# ETH_Switch.net
KiCad netlist of a schematic drawn in Altium Designer
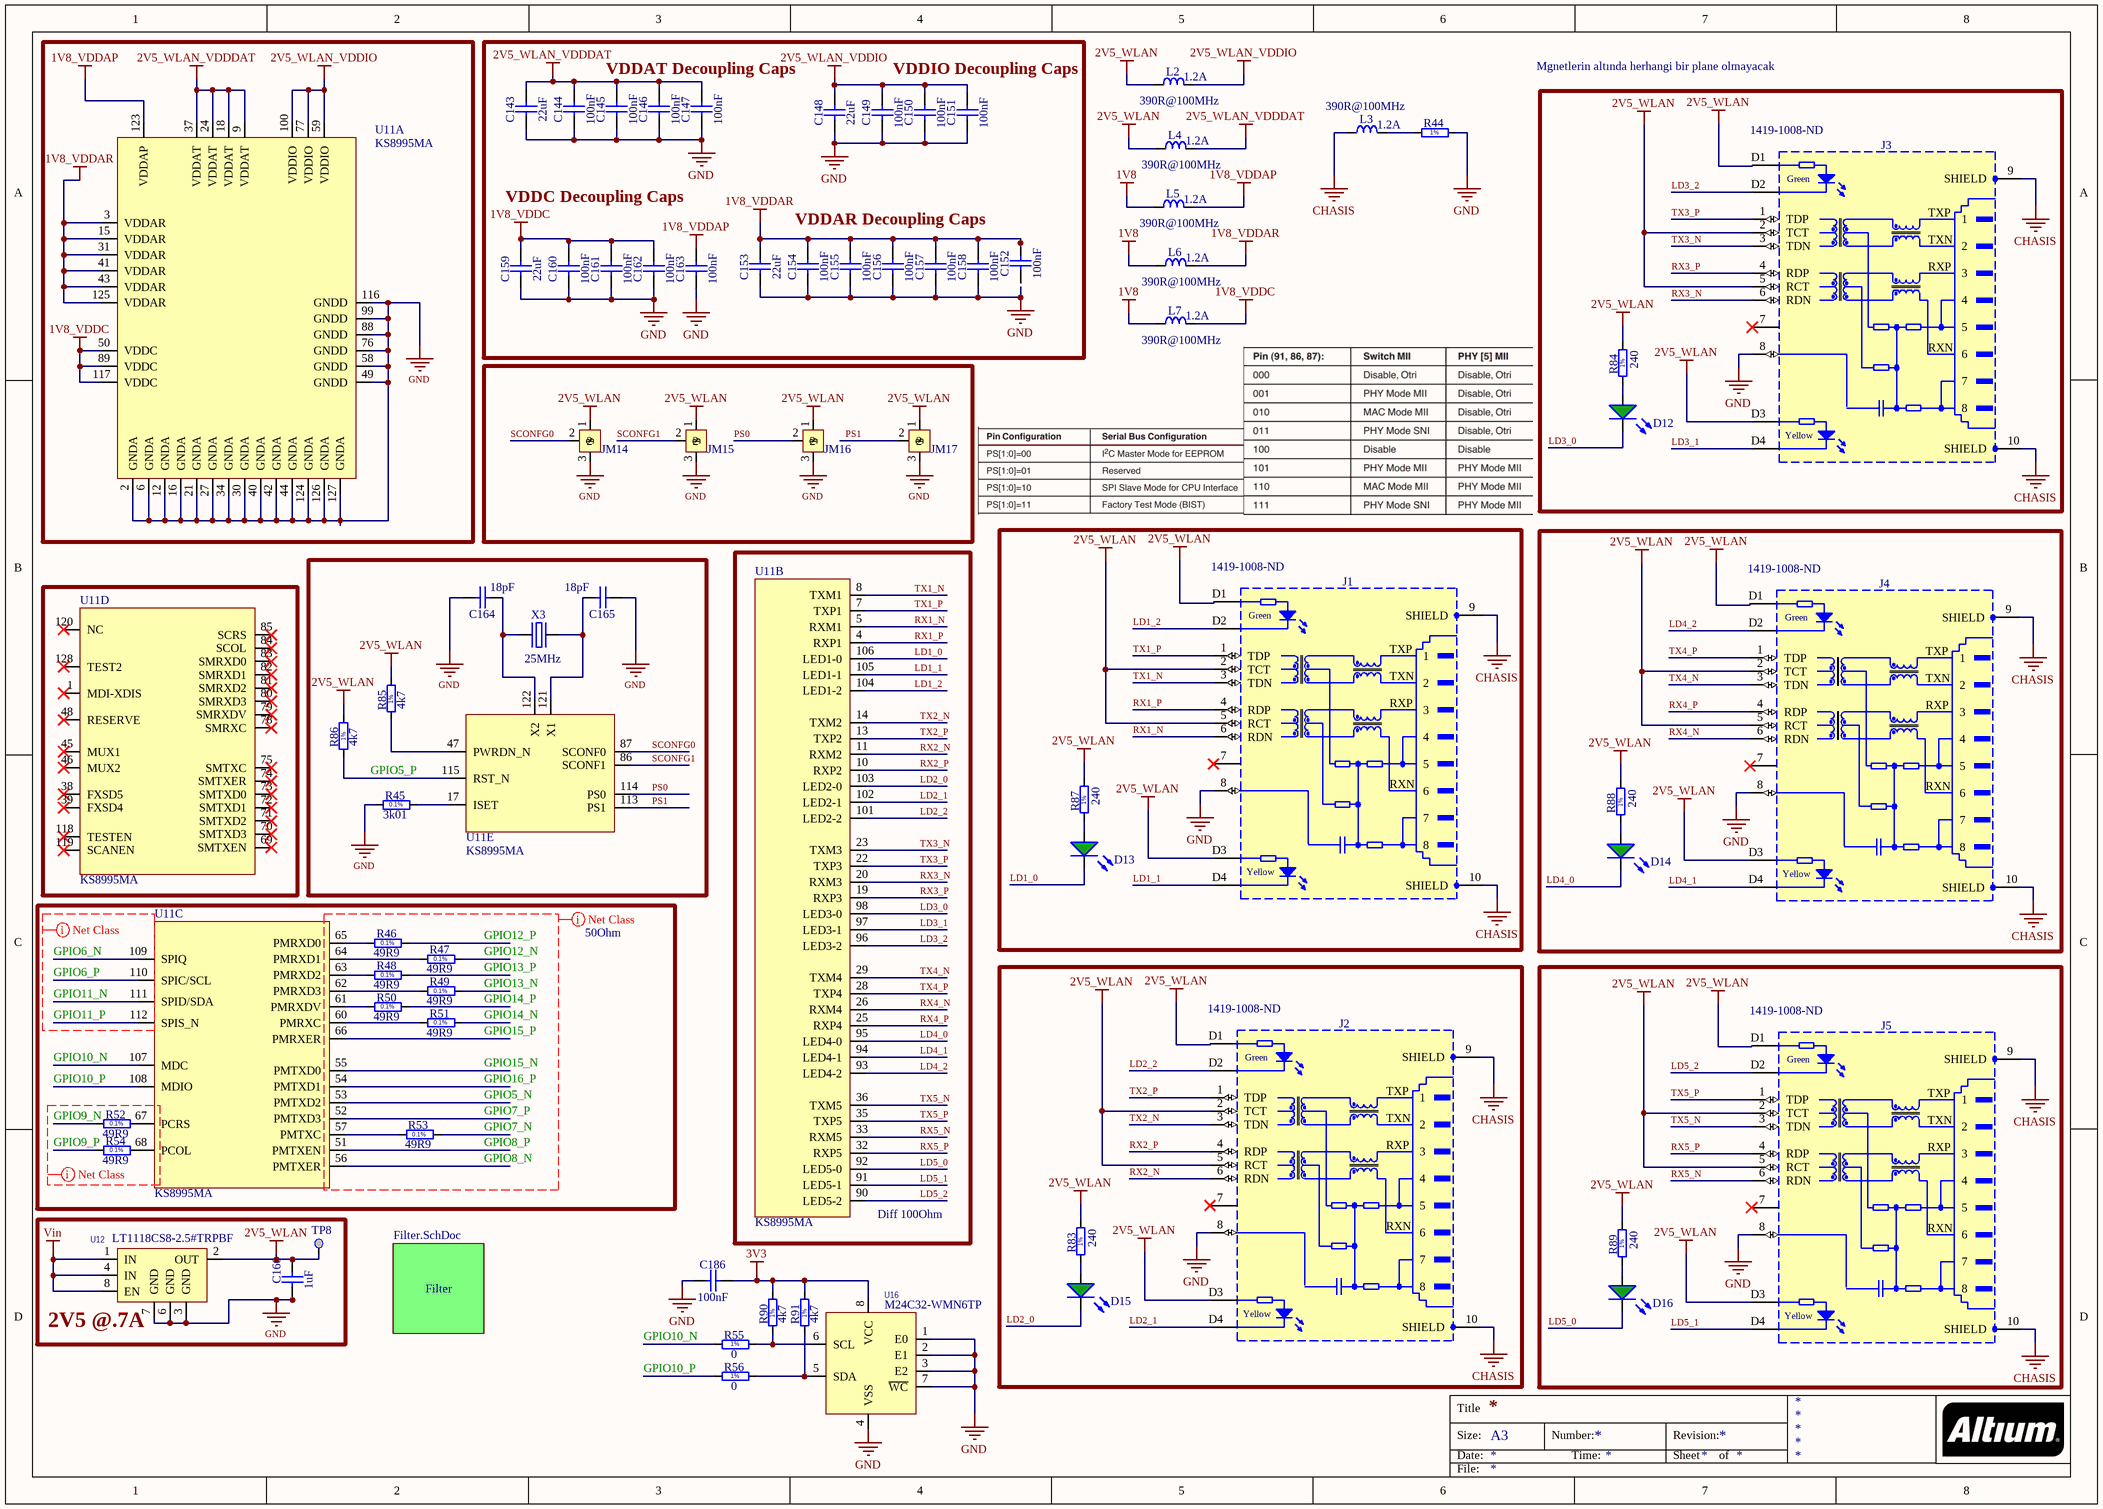
[diagram p0: ETH_Switch.SchDoc]

(export (version "E")
  (design (tool "Eeschema 10.0.6"))
  (components
    (comp (ref "C143")
      (value "22uF")
      (footprint "CAPC2012X135N")
      (description "Non-polarised capacitor")
      (fields (field (name "PART NUMBER") "CC0805_22UF_16V_10%_X5R") (field (name "VOLTAGE") "16V"))
      (libsource (lib "Capacitors") (part "Capacitor - non polarized"))
    )
    (comp (ref "C144")
      (value "100nF")
      (footprint "CAPC1608X87N")
      (description "Non-polarised capacitor")
      (fields (field (name "PART NUMBER") "CC0603_100NF_50V_10%_X7R") (field (name "VOLTAGE") "50V"))
      (libsource (lib "Capacitors") (part "Capacitor - non polarized"))
    )
    (comp (ref "C145")
      (value "100nF")
      (footprint "CAPC1608X87N")
      (description "Non-polarised capacitor")
      (fields (field (name "PART NUMBER") "CC0603_100NF_50V_10%_X7R") (field (name "VOLTAGE") "50V"))
      (libsource (lib "Capacitors") (part "Capacitor - non polarized"))
    )
    (comp (ref "C146")
      (value "100nF")
      (footprint "CAPC1608X87N")
      (description "Non-polarised capacitor")
      (fields (field (name "PART NUMBER") "CC0603_100NF_50V_10%_X7R") (field (name "VOLTAGE") "50V"))
      (libsource (lib "Capacitors") (part "Capacitor - non polarized"))
    )
    (comp (ref "C147")
      (value "100nF")
      (footprint "CAPC1608X87N")
      (description "Non-polarised capacitor")
      (fields (field (name "PART NUMBER") "CC0603_100NF_50V_10%_X7R") (field (name "VOLTAGE") "50V"))
      (libsource (lib "Capacitors") (part "Capacitor - non polarized"))
    )
    (comp (ref "C148")
      (value "22uF")
      (footprint "CAPC2012X135N")
      (description "Non-polarised capacitor")
      (fields (field (name "PART NUMBER") "CC0805_22UF_16V_10%_X5R") (field (name "VOLTAGE") "16V"))
      (libsource (lib "Capacitors") (part "Capacitor - non polarized"))
    )
    (comp (ref "C149")
      (value "100nF")
      (footprint "CAPC1608X87N")
      (description "Non-polarised capacitor")
      (fields (field (name "PART NUMBER") "CC0603_100NF_50V_10%_X7R") (field (name "VOLTAGE") "50V"))
      (libsource (lib "Capacitors") (part "Capacitor - non polarized"))
    )
    (comp (ref "C150")
      (value "100nF")
      (footprint "CAPC1608X87N")
      (description "Non-polarised capacitor")
      (fields (field (name "PART NUMBER") "CC0603_100NF_50V_10%_X7R") (field (name "VOLTAGE") "50V"))
      (libsource (lib "Capacitors") (part "Capacitor - non polarized"))
    )
    (comp (ref "C151")
      (value "100nF")
      (footprint "CAPC1608X87N")
      (description "Non-polarised capacitor")
      (fields (field (name "PART NUMBER") "CC0603_100NF_50V_10%_X7R") (field (name "VOLTAGE") "50V"))
      (libsource (lib "Capacitors") (part "Capacitor - non polarized"))
    )
    (comp (ref "C152")
      (value "100nF")
      (footprint "CAPC1608X87N")
      (description "Non-polarised capacitor")
      (fields (field (name "PART NUMBER") "CC0603_100NF_50V_10%_X7R") (field (name "VOLTAGE") "50V"))
      (libsource (lib "Capacitors") (part "Capacitor - non polarized"))
    )
    (comp (ref "C153")
      (value "22uF")
      (footprint "CAPC2012X135N")
      (description "Non-polarised capacitor")
      (fields (field (name "PART NUMBER") "CC0805_22UF_16V_10%_X5R") (field (name "VOLTAGE") "16V"))
      (libsource (lib "Capacitors") (part "Capacitor - non polarized"))
    )
    (comp (ref "C154")
      (value "100nF")
      (footprint "CAPC1608X87N")
      (description "Non-polarised capacitor")
      (fields (field (name "PART NUMBER") "CC0603_100NF_50V_10%_X7R") (field (name "VOLTAGE") "50V"))
      (libsource (lib "Capacitors") (part "Capacitor - non polarized"))
    )
    (comp (ref "C155")
      (value "100nF")
      (footprint "CAPC1608X87N")
      (description "Non-polarised capacitor")
      (fields (field (name "PART NUMBER") "CC0603_100NF_50V_10%_X7R") (field (name "VOLTAGE") "50V"))
      (libsource (lib "Capacitors") (part "Capacitor - non polarized"))
    )
    (comp (ref "C156")
      (value "100nF")
      (footprint "CAPC1608X87N")
      (description "Non-polarised capacitor")
      (fields (field (name "PART NUMBER") "CC0603_100NF_50V_10%_X7R") (field (name "VOLTAGE") "50V"))
      (libsource (lib "Capacitors") (part "Capacitor - non polarized"))
    )
    (comp (ref "C157")
      (value "100nF")
      (footprint "CAPC1608X87N")
      (description "Non-polarised capacitor")
      (fields (field (name "PART NUMBER") "CC0603_100NF_50V_10%_X7R") (field (name "VOLTAGE") "50V"))
      (libsource (lib "Capacitors") (part "Capacitor - non polarized"))
    )
    (comp (ref "C158")
      (value "100nF")
      (footprint "CAPC1608X87N")
      (description "Non-polarised capacitor")
      (fields (field (name "PART NUMBER") "CC0603_100NF_50V_10%_X7R") (field (name "VOLTAGE") "50V"))
      (libsource (lib "Capacitors") (part "Capacitor - non polarized"))
    )
    (comp (ref "C159")
      (value "22uF")
      (footprint "CAPC2012X135N")
      (description "Non-polarised capacitor")
      (fields (field (name "PART NUMBER") "CC0805_22UF_16V_10%_X5R") (field (name "VOLTAGE") "16V"))
      (libsource (lib "Capacitors") (part "Capacitor - non polarized"))
    )
    (comp (ref "C160")
      (value "100nF")
      (footprint "CAPC1608X87N")
      (description "Non-polarised capacitor")
      (fields (field (name "PART NUMBER") "CC0603_100NF_50V_10%_X7R") (field (name "VOLTAGE") "50V"))
      (libsource (lib "Capacitors") (part "Capacitor - non polarized"))
    )
    (comp (ref "C161")
      (value "100nF")
      (footprint "CAPC1608X87N")
      (description "Non-polarised capacitor")
      (fields (field (name "PART NUMBER") "CC0603_100NF_50V_10%_X7R") (field (name "VOLTAGE") "50V"))
      (libsource (lib "Capacitors") (part "Capacitor - non polarized"))
    )
    (comp (ref "C162")
      (value "100nF")
      (footprint "CAPC1608X87N")
      (description "Non-polarised capacitor")
      (fields (field (name "PART NUMBER") "CC0603_100NF_50V_10%_X7R") (field (name "VOLTAGE") "50V"))
      (libsource (lib "Capacitors") (part "Capacitor - non polarized"))
    )
    (comp (ref "C163")
      (value "100nF")
      (footprint "CAPC1608X87N")
      (description "Non-polarised capacitor")
      (fields (field (name "PART NUMBER") "CC0603_100NF_50V_10%_X7R") (field (name "VOLTAGE") "50V"))
      (libsource (lib "Capacitors") (part "Capacitor - non polarized"))
    )
    (comp (ref "C164")
      (value "18pF")
      (footprint "CAPC1608X87N")
      (description "Non-polarised capacitor")
      (fields (field (name "PART NUMBER") "CC0603_18PF_50V_5%_NP0") (field (name "VOLTAGE") "50V"))
      (libsource (lib "Capacitors") (part "Capacitor - non polarized"))
    )
    (comp (ref "C165")
      (value "18pF")
      (footprint "CAPC1608X87N")
      (description "Non-polarised capacitor")
      (fields (field (name "PART NUMBER") "CC0603_18PF_50V_5%_NP0") (field (name "VOLTAGE") "50V"))
      (libsource (lib "Capacitors") (part "Capacitor - non polarized"))
    )
    (comp (ref "C166")
      (value "1uF")
      (footprint "CAPC1608X87N")
      (description "Non-polarised capacitor")
      (fields (field (name "PART NUMBER") "CC0603_1UF_25V_10%_X7R") (field (name "VOLTAGE") "25V"))
      (libsource (lib "Capacitors") (part "Capacitor - non polarized"))
    )
    (comp (ref "C186")
      (value "100nF")
      (footprint "CAPC1608X87N")
      (description "Non-polarised capacitor")
      (fields (field (name "PART NUMBER") "CC0603_100NF_50V_10%_X7R") (field (name "VOLTAGE") "50V"))
      (libsource (lib "Capacitors") (part "Capacitor - non polarized"))
    )
    (comp (ref "D12")
      (value "LED0603")
      (footprint "LED0603")
      (description "Diode, LED, 0603, Green")
      (fields
        (field (name "MANUFACTURER PART NUMBER") "5988070100F")
        (field (name "MANUFACTURER") "Dialight")
      )
      (libsource (lib "SCHLIB") (part "LED0603"))
    )
    (comp (ref "D13")
      (value "LED0603")
      (footprint "LED0603")
      (description "Diode, LED, 0603, Green")
      (fields
        (field (name "MANUFACTURER PART NUMBER") "5988070100F")
        (field (name "MANUFACTURER") "Dialight")
      )
      (libsource (lib "SCHLIB") (part "LED0603"))
    )
    (comp (ref "D14")
      (value "LED0603")
      (footprint "LED0603")
      (description "Diode, LED, 0603, Green")
      (fields
        (field (name "MANUFACTURER PART NUMBER") "5988070100F")
        (field (name "MANUFACTURER") "Dialight")
      )
      (libsource (lib "SCHLIB") (part "LED0603"))
    )
    (comp (ref "D15")
      (value "LED0603")
      (footprint "LED0603")
      (description "Diode, LED, 0603, Green")
      (fields
        (field (name "MANUFACTURER PART NUMBER") "5988070100F")
        (field (name "MANUFACTURER") "Dialight")
      )
      (libsource (lib "SCHLIB") (part "LED0603"))
    )
    (comp (ref "D16")
      (value "LED0603")
      (footprint "LED0603")
      (description "Diode, LED, 0603, Green")
      (fields
        (field (name "MANUFACTURER PART NUMBER") "5988070100F")
        (field (name "MANUFACTURER") "Dialight")
      )
      (libsource (lib "SCHLIB") (part "LED0603"))
    )
    (comp (ref "J1")
      (value "RJ45")
      (footprint "TYCO_5-6605308-1")
      (fields
        (field (name "PART NUMBER") "TYCO_5-6605308-1")
        (field (name "MANUFACTURER") "TRP Connector B.V.")
        (field (name "MANUFACTURER PART NUMBER") "5-6605308-1")
        (field (name "SUPPLIER PART NUMBER") "1419-1008-ND")
      )
      (libsource (lib "Connectors") (part "TYCO_5-6605308-1"))
    )
    (comp (ref "J2")
      (value "RJ45")
      (footprint "TYCO_5-6605308-1")
      (fields
        (field (name "PART NUMBER") "TYCO_5-6605308-1")
        (field (name "MANUFACTURER") "TRP Connector B.V.")
        (field (name "MANUFACTURER PART NUMBER") "5-6605308-1")
        (field (name "SUPPLIER PART NUMBER") "1419-1008-ND")
      )
      (libsource (lib "Connectors") (part "TYCO_5-6605308-1"))
    )
    (comp (ref "J3")
      (value "RJ45")
      (footprint "TYCO_5-6605308-1")
      (fields
        (field (name "PART NUMBER") "TYCO_5-6605308-1")
        (field (name "MANUFACTURER") "TRP Connector B.V.")
        (field (name "MANUFACTURER PART NUMBER") "5-6605308-1")
        (field (name "SUPPLIER PART NUMBER") "1419-1008-ND")
      )
      (libsource (lib "Connectors") (part "TYCO_5-6605308-1"))
    )
    (comp (ref "J4")
      (value "RJ45")
      (footprint "TYCO_5-6605308-1")
      (fields
        (field (name "PART NUMBER") "TYCO_5-6605308-1")
        (field (name "MANUFACTURER") "TRP Connector B.V.")
        (field (name "MANUFACTURER PART NUMBER") "5-6605308-1")
        (field (name "SUPPLIER PART NUMBER") "1419-1008-ND")
      )
      (libsource (lib "Connectors") (part "TYCO_5-6605308-1"))
    )
    (comp (ref "J5")
      (value "RJ45")
      (footprint "TYCO_5-6605308-1")
      (fields
        (field (name "PART NUMBER") "TYCO_5-6605308-1")
        (field (name "MANUFACTURER") "TRP Connector B.V.")
        (field (name "MANUFACTURER PART NUMBER") "5-6605308-1")
        (field (name "SUPPLIER PART NUMBER") "1419-1008-ND")
      )
      (libsource (lib "Connectors") (part "TYCO_5-6605308-1"))
    )
    (comp (ref "JM14")
      (value "Jumper 0R")
      (footprint "JUMPER_0R")
      (libsource (lib "SCHLIB") (part "Jumper 0R"))
    )
    (comp (ref "JM15")
      (value "Jumper 0R")
      (footprint "JUMPER_0R")
      (libsource (lib "SCHLIB") (part "Jumper 0R"))
    )
    (comp (ref "JM16")
      (value "Jumper 0R")
      (footprint "JUMPER_0R")
      (libsource (lib "SCHLIB") (part "Jumper 0R"))
    )
    (comp (ref "JM17")
      (value "Jumper 0R")
      (footprint "JUMPER_0R")
      (libsource (lib "SCHLIB") (part "Jumper 0R"))
    )
    (comp (ref "L2")
      (value "390R@100MHz")
      (footprint "INDC1608X95N")
      (description "Inductor")
      (fields
        (field (name "PART NUMBER") "IND0603_TDK_MPZ1608R391A")
        (field (name "POWER") "1.2A")
        (field (name "TOLERANCE") "±25%")
      )
      (libsource (lib "Inductors & Transformers") (part "Inductor"))
    )
    (comp (ref "L3")
      (value "390R@100MHz")
      (footprint "INDC1608X95N")
      (description "Inductor")
      (fields
        (field (name "PART NUMBER") "IND0603_TDK_MPZ1608R391A")
        (field (name "POWER") "1.2A")
        (field (name "TOLERANCE") "±25%")
      )
      (libsource (lib "Inductors & Transformers") (part "Inductor"))
    )
    (comp (ref "L4")
      (value "390R@100MHz")
      (footprint "INDC1608X95N")
      (description "Inductor")
      (fields
        (field (name "PART NUMBER") "IND0603_TDK_MPZ1608R391A")
        (field (name "POWER") "1.2A")
        (field (name "TOLERANCE") "±25%")
      )
      (libsource (lib "Inductors & Transformers") (part "Inductor"))
    )
    (comp (ref "L5")
      (value "390R@100MHz")
      (footprint "INDC1608X95N")
      (description "Inductor")
      (fields
        (field (name "PART NUMBER") "IND0603_TDK_MPZ1608R391A")
        (field (name "POWER") "1.2A")
        (field (name "TOLERANCE") "±25%")
      )
      (libsource (lib "Inductors & Transformers") (part "Inductor"))
    )
    (comp (ref "L6")
      (value "390R@100MHz")
      (footprint "INDC1608X95N")
      (description "Inductor")
      (fields
        (field (name "PART NUMBER") "IND0603_TDK_MPZ1608R391A")
        (field (name "POWER") "1.2A")
        (field (name "TOLERANCE") "±25%")
      )
      (libsource (lib "Inductors & Transformers") (part "Inductor"))
    )
    (comp (ref "L7")
      (value "390R@100MHz")
      (footprint "INDC1608X95N")
      (description "Inductor")
      (fields
        (field (name "PART NUMBER") "IND0603_TDK_MPZ1608R391A")
        (field (name "POWER") "1.2A")
        (field (name "TOLERANCE") "±25%")
      )
      (libsource (lib "Inductors & Transformers") (part "Inductor"))
    )
    (comp (ref "R44")
      (value "0")
      (footprint "RESC3216X65N")
      (description "Resistor - 1%")
      (fields
        (field (name "PART NUMBER") "R1206_0R_JUMPER")
        (field (name "MANUFACTURER") "PANASONIC ELECTRONIC COMPONENTS")
      )
      (libsource (lib "Resistors") (part "Resistor - 1%"))
    )
    (comp (ref "R45")
      (value "3k01")
      (footprint "RESC1608X55N")
      (description "Resistor - 0.1%")
      (fields (field (name "PART NUMBER") "R0603_3K01_0.1%_0.063W_10PPM") (field (name "POWER") "0.063W"))
      (libsource (lib "Resistors") (part "Resistor - 0.1%"))
    )
    (comp (ref "R46")
      (value "49R9")
      (footprint "RESC1608X55N")
      (description "Resistor - 0.1%")
      (fields (field (name "PART NUMBER") "R0603_49R9_0.1%_0.063W_10PPM") (field (name "POWER") "0.063W"))
      (libsource (lib "Resistors") (part "Resistor - 0.1%"))
    )
    (comp (ref "R47")
      (value "49R9")
      (footprint "RESC1608X55N")
      (description "Resistor - 0.1%")
      (fields (field (name "PART NUMBER") "R0603_49R9_0.1%_0.063W_10PPM") (field (name "POWER") "0.063W"))
      (libsource (lib "Resistors") (part "Resistor - 0.1%"))
    )
    (comp (ref "R48")
      (value "49R9")
      (footprint "RESC1608X55N")
      (description "Resistor - 0.1%")
      (fields (field (name "PART NUMBER") "R0603_49R9_0.1%_0.063W_10PPM") (field (name "POWER") "0.063W"))
      (libsource (lib "Resistors") (part "Resistor - 0.1%"))
    )
    (comp (ref "R49")
      (value "49R9")
      (footprint "RESC1608X55N")
      (description "Resistor - 0.1%")
      (fields (field (name "PART NUMBER") "R0603_49R9_0.1%_0.063W_10PPM") (field (name "POWER") "0.063W"))
      (libsource (lib "Resistors") (part "Resistor - 0.1%"))
    )
    (comp (ref "R50")
      (value "49R9")
      (footprint "RESC1608X55N")
      (description "Resistor - 0.1%")
      (fields (field (name "PART NUMBER") "R0603_49R9_0.1%_0.063W_10PPM") (field (name "POWER") "0.063W"))
      (libsource (lib "Resistors") (part "Resistor - 0.1%"))
    )
    (comp (ref "R51")
      (value "49R9")
      (footprint "RESC1608X55N")
      (description "Resistor - 0.1%")
      (fields (field (name "PART NUMBER") "R0603_49R9_0.1%_0.063W_10PPM") (field (name "POWER") "0.063W"))
      (libsource (lib "Resistors") (part "Resistor - 0.1%"))
    )
    (comp (ref "R52")
      (value "49R9")
      (footprint "RESC1608X55N")
      (description "Resistor - 0.1%")
      (fields (field (name "PART NUMBER") "R0603_49R9_0.1%_0.063W_10PPM") (field (name "POWER") "0.063W"))
      (libsource (lib "Resistors") (part "Resistor - 0.1%"))
    )
    (comp (ref "R53")
      (value "49R9")
      (footprint "RESC1608X55N")
      (description "Resistor - 0.1%")
      (fields (field (name "PART NUMBER") "R0603_49R9_0.1%_0.063W_10PPM") (field (name "POWER") "0.063W"))
      (libsource (lib "Resistors") (part "Resistor - 0.1%"))
    )
    (comp (ref "R54")
      (value "49R9")
      (footprint "RESC1608X55N")
      (description "Resistor - 0.1%")
      (fields (field (name "PART NUMBER") "R0603_49R9_0.1%_0.063W_10PPM") (field (name "POWER") "0.063W"))
      (libsource (lib "Resistors") (part "Resistor - 0.1%"))
    )
    (comp (ref "R55")
      (value "0")
      (footprint "RESC1608X55N")
      (description "Resistor - 1%")
      (fields (field (name "PART NUMBER") "R0603_0R_JUMPER") (field (name "MANUFACTURER") "MULTICOMP"))
      (libsource (lib "Resistors") (part "Resistor - 1%"))
    )
    (comp (ref "R56")
      (value "0")
      (footprint "RESC1608X55N")
      (description "Resistor - 1%")
      (fields (field (name "PART NUMBER") "R0603_0R_JUMPER") (field (name "MANUFACTURER") "MULTICOMP"))
      (libsource (lib "Resistors") (part "Resistor - 1%"))
    )
    (comp (ref "R83")
      (value "~")
      (footprint "RESC1608X55N")
      (description "RES SMD 240 OHM 5% 1/10W 0603")
      (fields (field (name "MANUFACTURER") "Yageo") (field (name "RESISTANCE (OHMS)") "240"))
      (libsource (lib "Resistors") (part "Resistor - 1%"))
    )
    (comp (ref "R84")
      (value "~")
      (footprint "RESC1608X55N")
      (description "RES SMD 240 OHM 5% 1/10W 0603")
      (fields (field (name "MANUFACTURER") "Yageo") (field (name "RESISTANCE (OHMS)") "240"))
      (libsource (lib "Resistors") (part "Resistor - 1%"))
    )
    (comp (ref "R85")
      (value "4k7")
      (footprint "RESC1608X55N")
      (description "Resistor - 1%")
      (fields (field (name "PART NUMBER") "R0603_4K7_1%_0.1W_100PPM") (field (name "POWER") "0.1W"))
      (libsource (lib "Resistors") (part "Resistor - 1%"))
    )
    (comp (ref "R86")
      (value "4k7")
      (footprint "RESC1608X55N")
      (description "Resistor - 1%")
      (fields (field (name "PART NUMBER") "R0603_4K7_1%_0.1W_100PPM") (field (name "POWER") "0.1W"))
      (libsource (lib "Resistors") (part "Resistor - 1%"))
    )
    (comp (ref "R87")
      (value "~")
      (footprint "RESC1608X55N")
      (description "RES SMD 240 OHM 5% 1/10W 0603")
      (fields (field (name "MANUFACTURER") "Yageo") (field (name "RESISTANCE (OHMS)") "240"))
      (libsource (lib "Resistors") (part "Resistor - 1%"))
    )
    (comp (ref "R88")
      (value "~")
      (footprint "RESC1608X55N")
      (description "RES SMD 240 OHM 5% 1/10W 0603")
      (fields (field (name "MANUFACTURER") "Yageo") (field (name "RESISTANCE (OHMS)") "240"))
      (libsource (lib "Resistors") (part "Resistor - 1%"))
    )
    (comp (ref "R89")
      (value "~")
      (footprint "RESC1608X55N")
      (description "RES SMD 240 OHM 5% 1/10W 0603")
      (fields (field (name "MANUFACTURER") "Yageo") (field (name "RESISTANCE (OHMS)") "240"))
      (libsource (lib "Resistors") (part "Resistor - 1%"))
    )
    (comp (ref "R90")
      (value "4k7")
      (footprint "RESC1608X55N")
      (description "Resistor - 1%")
      (fields (field (name "PART NUMBER") "R0603_4K7_1%_0.1W_100PPM") (field (name "POWER") "0.1W"))
      (libsource (lib "Resistors") (part "Resistor - 1%"))
    )
    (comp (ref "R91")
      (value "4k7")
      (footprint "RESC1608X55N")
      (description "Resistor - 1%")
      (fields (field (name "PART NUMBER") "R0603_4K7_1%_0.1W_100PPM") (field (name "POWER") "0.1W"))
      (libsource (lib "Resistors") (part "Resistor - 1%"))
    )
    (comp (ref "TP8")
      (value "TP")
      (footprint "TP")
      (description "Test Point")
      (libsource (lib "SCHLIB") (part "Test Point"))
    )
    (comp (ref "U11")
      (value "KS8995MA")
      (footprint "KS8995MA")
      (description "IC SWITCH 10/100 5PORT 128PQFP")
      (fields (field (name "MANUFACTURER") "Microchip Technology"))
      (libsource (lib "SCHLIB") (part "KS8995MA"))
    )
    (comp (ref "U12")
      (value "LT1118CS8-2.5")
      (footprint "SO8")
      (description "IC REG LDO 2.5V 0.8A 8SOIC")
      (fields
        (field (name "MANUFACTURER") "Linear Technology")
        (field (name "MANUFACTURER PART NUMBER") "LT1118CS8-2.5#TRPBF")
      )
      (libsource (lib "SCHLIB") (part "LT1118CS8-2.5"))
    )
    (comp (ref "U16")
      (value "M24C32-WMN6TP")
      (footprint "SO8")
      (description "IC EEPROM 32KBIT 400KHZ 8SO")
      (fields
        (field (name "MANUFACTURER") "STMicroelectronics")
        (field (name "MANUFACTURER PART NUMBER") "M24C32-WMN6TP")
      )
      (libsource (lib "SCHLIB") (part "M24C32-WMN6TP"))
    )
    (comp (ref "X3")
      (value "25MHz")
      (footprint "XTAL1140X470X160N")
      (description "Quartz Crystal")
      (fields
        (field (name "PART NUMBER") "XTAL_25MHZ_ABRACON_ABLS-25.000MHZ-B2F-T")
        (field (name "MANUFACTURER") "Abracon LLC")
      )
      (libsource (lib "ICs And Semiconductors") (part "Quartz Crystal"))
    )
  )
  (nets
    (net (code "1") (name "/GPIO5_N") (class "Default")
      (node (ref "U11") (pin "53") (pinfunction "PMTXD2_53") (pintype "passive"))
    )
    (net (code "2") (name "/GPIO5_P") (class "Default")
      (node (ref "R86") (pin "1") (pinfunction "1_1") (pintype "passive"))
      (node (ref "U11") (pin "115") (pinfunction "RST_N_115") (pintype "passive"))
    )
    (net (code "3") (name "/GPIO6_N") (class "Default")
      (node (ref "U11") (pin "109") (pinfunction "SPIQ_109") (pintype "passive"))
    )
    (net (code "4") (name "/GPIO6_P") (class "Default")
      (node (ref "U11") (pin "110") (pinfunction "SPIC/SCL_110") (pintype "passive"))
    )
    (net (code "5") (name "/GPIO7_N") (class "Default")
      (node (ref "R53") (pin "2") (pinfunction "2_2") (pintype "passive"))
    )
    (net (code "6") (name "/GPIO7_P") (class "Default")
      (node (ref "U11") (pin "52") (pinfunction "PMTXD3_52") (pintype "passive"))
    )
    (net (code "7") (name "/GPIO8_N") (class "Default")
      (node (ref "U11") (pin "56") (pinfunction "PMTXER_56") (pintype "passive"))
    )
    (net (code "8") (name "/GPIO8_P") (class "Default")
      (node (ref "U11") (pin "51") (pinfunction "PMTXEN_51") (pintype "passive"))
    )
    (net (code "9") (name "/GPIO9_N") (class "Default")
      (node (ref "R52") (pin "1") (pinfunction "1_1") (pintype "passive"))
    )
    (net (code "10") (name "/GPIO9_P") (class "Default")
      (node (ref "R54") (pin "1") (pinfunction "1_1") (pintype "passive"))
    )
    (net (code "11") (name "/GPIO10_N") (class "Default")
      (node (ref "R55") (pin "1") (pinfunction "1_1") (pintype "passive"))
      (node (ref "U11") (pin "107") (pinfunction "MDC_107") (pintype "passive"))
    )
    (net (code "12") (name "/GPIO10_P") (class "Default")
      (node (ref "R56") (pin "1") (pinfunction "1_1") (pintype "passive"))
      (node (ref "U11") (pin "108") (pinfunction "MDIO_108") (pintype "passive"))
    )
    (net (code "13") (name "/GPIO11_N") (class "Default")
      (node (ref "U11") (pin "111") (pinfunction "SPID/SDA_111") (pintype "passive"))
    )
    (net (code "14") (name "/GPIO11_P") (class "Default")
      (node (ref "U11") (pin "112") (pinfunction "SPIS_N_112") (pintype "passive"))
    )
    (net (code "15") (name "/GPIO12_N") (class "Default")
      (node (ref "R47") (pin "2") (pinfunction "2_2") (pintype "passive"))
    )
    (net (code "16") (name "/GPIO12_P") (class "Default")
      (node (ref "R46") (pin "2") (pinfunction "2_2") (pintype "passive"))
    )
    (net (code "17") (name "/GPIO13_N") (class "Default")
      (node (ref "R49") (pin "2") (pinfunction "2_2") (pintype "passive"))
    )
    (net (code "18") (name "/GPIO13_P") (class "Default")
      (node (ref "R48") (pin "2") (pinfunction "2_2") (pintype "passive"))
    )
    (net (code "19") (name "/GPIO14_N") (class "Default")
      (node (ref "R51") (pin "2") (pinfunction "2_2") (pintype "passive"))
    )
    (net (code "20") (name "/GPIO14_P") (class "Default")
      (node (ref "R50") (pin "2") (pinfunction "2_2") (pintype "passive"))
    )
    (net (code "21") (name "/GPIO15_N") (class "Default")
      (node (ref "U11") (pin "55") (pinfunction "PMTXD0_55") (pintype "passive"))
    )
    (net (code "22") (name "/GPIO15_P") (class "Default")
      (node (ref "U11") (pin "66") (pinfunction "PMRXER_66") (pintype "passive"))
    )
    (net (code "23") (name "/GPIO16_P") (class "Default")
      (node (ref "U11") (pin "54") (pinfunction "PMTXD1_54") (pintype "passive"))
    )
    (net (code "24") (name "/LD1_0") (class "Default")
      (node (ref "D13") (pin "K") (pinfunction "K_K") (pintype "passive"))
      (node (ref "U11") (pin "106") (pinfunction "LED1-0_106") (pintype "passive"))
    )
    (net (code "25") (name "/LD1_1") (class "Default")
      (node (ref "J1") (pin "D4") (pinfunction "D4_D4") (pintype "passive"))
      (node (ref "U11") (pin "105") (pinfunction "LED1-1_105") (pintype "passive"))
    )
    (net (code "26") (name "/LD1_2") (class "Default")
      (node (ref "J1") (pin "D2") (pinfunction "D2_D2") (pintype "passive"))
      (node (ref "U11") (pin "104") (pinfunction "LED1-2_104") (pintype "passive"))
    )
    (net (code "27") (name "/LD2_0") (class "Default")
      (node (ref "D15") (pin "K") (pinfunction "K_K") (pintype "passive"))
      (node (ref "U11") (pin "103") (pinfunction "LED2-0_103") (pintype "passive"))
    )
    (net (code "28") (name "/LD2_1") (class "Default")
      (node (ref "J2") (pin "D4") (pinfunction "D4_D4") (pintype "passive"))
      (node (ref "U11") (pin "102") (pinfunction "LED2-1_102") (pintype "passive"))
    )
    (net (code "29") (name "/LD2_2") (class "Default")
      (node (ref "J2") (pin "D2") (pinfunction "D2_D2") (pintype "passive"))
      (node (ref "U11") (pin "101") (pinfunction "LED2-2_101") (pintype "passive"))
    )
    (net (code "30") (name "/LD3_0") (class "Default")
      (node (ref "D12") (pin "K") (pinfunction "K_K") (pintype "passive"))
      (node (ref "U11") (pin "98") (pinfunction "LED3-0_98") (pintype "passive"))
    )
    (net (code "31") (name "/LD3_1") (class "Default")
      (node (ref "J3") (pin "D4") (pinfunction "D4_D4") (pintype "passive"))
      (node (ref "U11") (pin "97") (pinfunction "LED3-1_97") (pintype "passive"))
    )
    (net (code "32") (name "/LD3_2") (class "Default")
      (node (ref "J3") (pin "D2") (pinfunction "D2_D2") (pintype "passive"))
      (node (ref "U11") (pin "96") (pinfunction "LED3-2_96") (pintype "passive"))
    )
    (net (code "33") (name "/LD4_0") (class "Default")
      (node (ref "D14") (pin "K") (pinfunction "K_K") (pintype "passive"))
      (node (ref "U11") (pin "95") (pinfunction "LED4-0_95") (pintype "passive"))
    )
    (net (code "34") (name "/LD4_1") (class "Default")
      (node (ref "J4") (pin "D4") (pinfunction "D4_D4") (pintype "passive"))
      (node (ref "U11") (pin "94") (pinfunction "LED4-1_94") (pintype "passive"))
    )
    (net (code "35") (name "/LD4_2") (class "Default")
      (node (ref "J4") (pin "D2") (pinfunction "D2_D2") (pintype "passive"))
      (node (ref "U11") (pin "93") (pinfunction "LED4-2_93") (pintype "passive"))
    )
    (net (code "36") (name "/LD5_0") (class "Default")
      (node (ref "D16") (pin "K") (pinfunction "K_K") (pintype "passive"))
      (node (ref "U11") (pin "92") (pinfunction "LED5-0_92") (pintype "passive"))
    )
    (net (code "37") (name "/LD5_1") (class "Default")
      (node (ref "J5") (pin "D4") (pinfunction "D4_D4") (pintype "passive"))
      (node (ref "U11") (pin "91") (pinfunction "LED5-1_91") (pintype "passive"))
    )
    (net (code "38") (name "/LD5_2") (class "Default")
      (node (ref "J5") (pin "D2") (pinfunction "D2_D2") (pintype "passive"))
      (node (ref "U11") (pin "90") (pinfunction "LED5-2_90") (pintype "passive"))
    )
    (net (code "39") (name "/PS0") (class "Default")
      (node (ref "JM16") (pin "2") (pinfunction "2_2") (pintype "passive"))
      (node (ref "U11") (pin "114") (pinfunction "PS0_114") (pintype "passive"))
    )
    (net (code "40") (name "/PS1") (class "Default")
      (node (ref "JM17") (pin "2") (pinfunction "2_2") (pintype "passive"))
      (node (ref "U11") (pin "113") (pinfunction "PS1_113") (pintype "passive"))
    )
    (net (code "41") (name "/RX1_N") (class "Default")
      (node (ref "J1") (pin "6") (pinfunction "RDN_6") (pintype "bidirectional"))
      (node (ref "U11") (pin "5") (pinfunction "RXM1_5") (pintype "passive"))
    )
    (net (code "42") (name "/RX1_P") (class "Default")
      (node (ref "J1") (pin "4") (pinfunction "RDP_4") (pintype "bidirectional"))
      (node (ref "U11") (pin "4") (pinfunction "RXP1_4") (pintype "passive"))
    )
    (net (code "43") (name "/RX2_N") (class "Default")
      (node (ref "J2") (pin "6") (pinfunction "RDN_6") (pintype "bidirectional"))
      (node (ref "U11") (pin "11") (pinfunction "RXM2_11") (pintype "passive"))
    )
    (net (code "44") (name "/RX2_P") (class "Default")
      (node (ref "J2") (pin "4") (pinfunction "RDP_4") (pintype "bidirectional"))
      (node (ref "U11") (pin "10") (pinfunction "RXP2_10") (pintype "passive"))
    )
    (net (code "45") (name "/RX3_N") (class "Default")
      (node (ref "J3") (pin "6") (pinfunction "RDN_6") (pintype "bidirectional"))
      (node (ref "U11") (pin "20") (pinfunction "RXM3_20") (pintype "passive"))
    )
    (net (code "46") (name "/RX3_P") (class "Default")
      (node (ref "J3") (pin "4") (pinfunction "RDP_4") (pintype "bidirectional"))
      (node (ref "U11") (pin "19") (pinfunction "RXP3_19") (pintype "passive"))
    )
    (net (code "47") (name "/RX4_N") (class "Default")
      (node (ref "J4") (pin "6") (pinfunction "RDN_6") (pintype "bidirectional"))
      (node (ref "U11") (pin "26") (pinfunction "RXM4_26") (pintype "passive"))
    )
    (net (code "48") (name "/RX4_P") (class "Default")
      (node (ref "J4") (pin "4") (pinfunction "RDP_4") (pintype "bidirectional"))
      (node (ref "U11") (pin "25") (pinfunction "RXP4_25") (pintype "passive"))
    )
    (net (code "49") (name "/RX5_N") (class "Default")
      (node (ref "J5") (pin "6") (pinfunction "RDN_6") (pintype "bidirectional"))
      (node (ref "U11") (pin "33") (pinfunction "RXM5_33") (pintype "passive"))
    )
    (net (code "50") (name "/RX5_P") (class "Default")
      (node (ref "J5") (pin "4") (pinfunction "RDP_4") (pintype "bidirectional"))
      (node (ref "U11") (pin "32") (pinfunction "RXP5_32") (pintype "passive"))
    )
    (net (code "51") (name "/SCONFG0") (class "Default")
      (node (ref "JM14") (pin "2") (pinfunction "2_2") (pintype "passive"))
      (node (ref "U11") (pin "87") (pinfunction "SCONF0_87") (pintype "passive"))
    )
    (net (code "52") (name "/SCONFG1") (class "Default")
      (node (ref "JM15") (pin "2") (pinfunction "2_2") (pintype "passive"))
      (node (ref "U11") (pin "86") (pinfunction "SCONF1_86") (pintype "passive"))
    )
    (net (code "53") (name "/TX1_N") (class "Default")
      (node (ref "J1") (pin "3") (pinfunction "TDN_3") (pintype "bidirectional"))
      (node (ref "U11") (pin "8") (pinfunction "TXM1_8") (pintype "passive"))
    )
    (net (code "54") (name "/TX1_P") (class "Default")
      (node (ref "J1") (pin "1") (pinfunction "TDP_1") (pintype "bidirectional"))
      (node (ref "U11") (pin "7") (pinfunction "TXP1_7") (pintype "passive"))
    )
    (net (code "55") (name "/TX2_N") (class "Default")
      (node (ref "J2") (pin "3") (pinfunction "TDN_3") (pintype "bidirectional"))
      (node (ref "U11") (pin "14") (pinfunction "TXM2_14") (pintype "passive"))
    )
    (net (code "56") (name "/TX2_P") (class "Default")
      (node (ref "J2") (pin "1") (pinfunction "TDP_1") (pintype "bidirectional"))
      (node (ref "U11") (pin "13") (pinfunction "TXP2_13") (pintype "passive"))
    )
    (net (code "57") (name "/TX3_N") (class "Default")
      (node (ref "J3") (pin "3") (pinfunction "TDN_3") (pintype "bidirectional"))
      (node (ref "U11") (pin "23") (pinfunction "TXM3_23") (pintype "passive"))
    )
    (net (code "58") (name "/TX3_P") (class "Default")
      (node (ref "J3") (pin "1") (pinfunction "TDP_1") (pintype "bidirectional"))
      (node (ref "U11") (pin "22") (pinfunction "TXP3_22") (pintype "passive"))
    )
    (net (code "59") (name "/TX4_N") (class "Default")
      (node (ref "J4") (pin "3") (pinfunction "TDN_3") (pintype "bidirectional"))
      (node (ref "U11") (pin "29") (pinfunction "TXM4_29") (pintype "passive"))
    )
    (net (code "60") (name "/TX4_P") (class "Default")
      (node (ref "J4") (pin "1") (pinfunction "TDP_1") (pintype "bidirectional"))
      (node (ref "U11") (pin "28") (pinfunction "TXP4_28") (pintype "passive"))
    )
    (net (code "61") (name "/TX5_N") (class "Default")
      (node (ref "J5") (pin "3") (pinfunction "TDN_3") (pintype "bidirectional"))
      (node (ref "U11") (pin "36") (pinfunction "TXM5_36") (pintype "passive"))
    )
    (net (code "62") (name "/TX5_P") (class "Default")
      (node (ref "J5") (pin "1") (pinfunction "TDP_1") (pintype "bidirectional"))
      (node (ref "U11") (pin "35") (pinfunction "TXP5_35") (pintype "passive"))
    )
    (net (code "63") (name "1V8") (class "Default")
      (node (ref "L5") (pin "1") (pinfunction "1_1") (pintype "passive"))
      (node (ref "L6") (pin "1") (pinfunction "1_1") (pintype "passive"))
      (node (ref "L7") (pin "1") (pinfunction "1_1") (pintype "passive"))
    )
    (net (code "64") (name "1V8_VDDAP") (class "Default")
      (node (ref "C163") (pin "2") (pinfunction "2_2") (pintype "passive"))
      (node (ref "L5") (pin "2") (pinfunction "2_2") (pintype "passive"))
      (node (ref "U11") (pin "123") (pinfunction "VDDAP_123") (pintype "passive"))
    )
    (net (code "65") (name "1V8_VDDAR") (class "Default")
      (node (ref "C152") (pin "2") (pinfunction "2_2") (pintype "passive"))
      (node (ref "C153") (pin "2") (pinfunction "2_2") (pintype "passive"))
      (node (ref "C154") (pin "2") (pinfunction "2_2") (pintype "passive"))
      (node (ref "C155") (pin "2") (pinfunction "2_2") (pintype "passive"))
      (node (ref "C156") (pin "2") (pinfunction "2_2") (pintype "passive"))
      (node (ref "C157") (pin "2") (pinfunction "2_2") (pintype "passive"))
      (node (ref "C158") (pin "2") (pinfunction "2_2") (pintype "passive"))
      (node (ref "L6") (pin "2") (pinfunction "2_2") (pintype "passive"))
      (node (ref "U11") (pin "125") (pinfunction "VDDAR_125") (pintype "passive"))
      (node (ref "U11") (pin "15") (pinfunction "VDDAR_15") (pintype "passive"))
      (node (ref "U11") (pin "3") (pinfunction "VDDAR_3") (pintype "passive"))
      (node (ref "U11") (pin "31") (pinfunction "VDDAR_31") (pintype "passive"))
      (node (ref "U11") (pin "41") (pinfunction "VDDAR_41") (pintype "passive"))
      (node (ref "U11") (pin "43") (pinfunction "VDDAR_43") (pintype "passive"))
    )
    (net (code "66") (name "1V8_VDDC") (class "Default")
      (node (ref "C159") (pin "2") (pinfunction "2_2") (pintype "passive"))
      (node (ref "C160") (pin "2") (pinfunction "2_2") (pintype "passive"))
      (node (ref "C161") (pin "2") (pinfunction "2_2") (pintype "passive"))
      (node (ref "C162") (pin "2") (pinfunction "2_2") (pintype "passive"))
      (node (ref "L7") (pin "2") (pinfunction "2_2") (pintype "passive"))
      (node (ref "U11") (pin "117") (pinfunction "VDDC_117") (pintype "passive"))
      (node (ref "U11") (pin "50") (pinfunction "VDDC_50") (pintype "passive"))
      (node (ref "U11") (pin "89") (pinfunction "VDDC_89") (pintype "passive"))
    )
    (net (code "67") (name "2V5_WLAN") (class "Default")
      (node (ref "C166") (pin "2") (pinfunction "2_2") (pintype "passive"))
      (node (ref "J1") (pin "2") (pinfunction "TCT_2") (pintype "bidirectional"))
      (node (ref "J1") (pin "5") (pinfunction "RCT_5") (pintype "bidirectional"))
      (node (ref "J1") (pin "D1") (pinfunction "D1_D1") (pintype "passive"))
      (node (ref "J1") (pin "D3") (pinfunction "D3_D3") (pintype "passive"))
      (node (ref "J2") (pin "2") (pinfunction "TCT_2") (pintype "bidirectional"))
      (node (ref "J2") (pin "5") (pinfunction "RCT_5") (pintype "bidirectional"))
      (node (ref "J2") (pin "D1") (pinfunction "D1_D1") (pintype "passive"))
      (node (ref "J2") (pin "D3") (pinfunction "D3_D3") (pintype "passive"))
      (node (ref "J3") (pin "2") (pinfunction "TCT_2") (pintype "bidirectional"))
      (node (ref "J3") (pin "5") (pinfunction "RCT_5") (pintype "bidirectional"))
      (node (ref "J3") (pin "D1") (pinfunction "D1_D1") (pintype "passive"))
      (node (ref "J3") (pin "D3") (pinfunction "D3_D3") (pintype "passive"))
      (node (ref "J4") (pin "2") (pinfunction "TCT_2") (pintype "bidirectional"))
      (node (ref "J4") (pin "5") (pinfunction "RCT_5") (pintype "bidirectional"))
      (node (ref "J4") (pin "D1") (pinfunction "D1_D1") (pintype "passive"))
      (node (ref "J4") (pin "D3") (pinfunction "D3_D3") (pintype "passive"))
      (node (ref "J5") (pin "2") (pinfunction "TCT_2") (pintype "bidirectional"))
      (node (ref "J5") (pin "5") (pinfunction "RCT_5") (pintype "bidirectional"))
      (node (ref "J5") (pin "D1") (pinfunction "D1_D1") (pintype "passive"))
      (node (ref "J5") (pin "D3") (pinfunction "D3_D3") (pintype "passive"))
      (node (ref "JM14") (pin "1") (pinfunction "1_1") (pintype "passive"))
      (node (ref "JM15") (pin "1") (pinfunction "1_1") (pintype "passive"))
      (node (ref "JM16") (pin "1") (pinfunction "1_1") (pintype "passive"))
      (node (ref "JM17") (pin "1") (pinfunction "1_1") (pintype "passive"))
      (node (ref "L2") (pin "1") (pinfunction "1_1") (pintype "passive"))
      (node (ref "L4") (pin "1") (pinfunction "1_1") (pintype "passive"))
      (node (ref "R83") (pin "2") (pinfunction "2_2") (pintype "passive"))
      (node (ref "R84") (pin "2") (pinfunction "2_2") (pintype "passive"))
      (node (ref "R85") (pin "2") (pinfunction "2_2") (pintype "passive"))
      (node (ref "R86") (pin "2") (pinfunction "2_2") (pintype "passive"))
      (node (ref "R87") (pin "2") (pinfunction "2_2") (pintype "passive"))
      (node (ref "R88") (pin "2") (pinfunction "2_2") (pintype "passive"))
      (node (ref "R89") (pin "2") (pinfunction "2_2") (pintype "passive"))
      (node (ref "TP8") (pin "1") (pinfunction "1_1") (pintype "passive"))
      (node (ref "U12") (pin "2") (pinfunction "OUT_2") (pintype "passive"))
    )
    (net (code "68") (name "2V5_WLAN_VDDDAT") (class "Default")
      (node (ref "C143") (pin "2") (pinfunction "2_2") (pintype "passive"))
      (node (ref "C144") (pin "2") (pinfunction "2_2") (pintype "passive"))
      (node (ref "C145") (pin "2") (pinfunction "2_2") (pintype "passive"))
      (node (ref "C146") (pin "2") (pinfunction "2_2") (pintype "passive"))
      (node (ref "C147") (pin "2") (pinfunction "2_2") (pintype "passive"))
      (node (ref "L4") (pin "2") (pinfunction "2_2") (pintype "passive"))
      (node (ref "U11") (pin "18") (pinfunction "VDDAT_18") (pintype "passive"))
      (node (ref "U11") (pin "24") (pinfunction "VDDAT_24") (pintype "passive"))
      (node (ref "U11") (pin "37") (pinfunction "VDDAT_37") (pintype "passive"))
      (node (ref "U11") (pin "9") (pinfunction "VDDAT_9") (pintype "passive"))
    )
    (net (code "69") (name "2V5_WLAN_VDDIO") (class "Default")
      (node (ref "C148") (pin "2") (pinfunction "2_2") (pintype "passive"))
      (node (ref "C149") (pin "2") (pinfunction "2_2") (pintype "passive"))
      (node (ref "C150") (pin "2") (pinfunction "2_2") (pintype "passive"))
      (node (ref "C151") (pin "2") (pinfunction "2_2") (pintype "passive"))
      (node (ref "L2") (pin "2") (pinfunction "2_2") (pintype "passive"))
      (node (ref "U11") (pin "100") (pinfunction "VDDIO_100") (pintype "passive"))
      (node (ref "U11") (pin "59") (pinfunction "VDDIO_59") (pintype "passive"))
      (node (ref "U11") (pin "77") (pinfunction "VDDIO_77") (pintype "passive"))
    )
    (net (code "70") (name "3V3") (class "Default")
      (node (ref "C186") (pin "2") (pinfunction "2_2") (pintype "passive"))
      (node (ref "R90") (pin "2") (pinfunction "2_2") (pintype "passive"))
      (node (ref "R91") (pin "2") (pinfunction "2_2") (pintype "passive"))
      (node (ref "U16") (pin "8") (pinfunction "VCC_8") (pintype "passive"))
    )
    (net (code "71") (name "CHASIS") (class "Default")
      (node (ref "J1") (pin "10") (pinfunction "SHIELD_10") (pintype "power_in"))
      (node (ref "J1") (pin "9") (pinfunction "SHIELD_9") (pintype "power_in"))
      (node (ref "J2") (pin "10") (pinfunction "SHIELD_10") (pintype "power_in"))
      (node (ref "J2") (pin "9") (pinfunction "SHIELD_9") (pintype "power_in"))
      (node (ref "J3") (pin "10") (pinfunction "SHIELD_10") (pintype "power_in"))
      (node (ref "J3") (pin "9") (pinfunction "SHIELD_9") (pintype "power_in"))
      (node (ref "J4") (pin "10") (pinfunction "SHIELD_10") (pintype "power_in"))
      (node (ref "J4") (pin "9") (pinfunction "SHIELD_9") (pintype "power_in"))
      (node (ref "J5") (pin "10") (pinfunction "SHIELD_10") (pintype "power_in"))
      (node (ref "J5") (pin "9") (pinfunction "SHIELD_9") (pintype "power_in"))
      (node (ref "L3") (pin "1") (pinfunction "1_1") (pintype "passive"))
    )
    (net (code "72") (name "GND") (class "Default")
      (node (ref "C143") (pin "1") (pinfunction "1_1") (pintype "passive"))
      (node (ref "C144") (pin "1") (pinfunction "1_1") (pintype "passive"))
      (node (ref "C145") (pin "1") (pinfunction "1_1") (pintype "passive"))
      (node (ref "C146") (pin "1") (pinfunction "1_1") (pintype "passive"))
      (node (ref "C147") (pin "1") (pinfunction "1_1") (pintype "passive"))
      (node (ref "C148") (pin "1") (pinfunction "1_1") (pintype "passive"))
      (node (ref "C149") (pin "1") (pinfunction "1_1") (pintype "passive"))
      (node (ref "C150") (pin "1") (pinfunction "1_1") (pintype "passive"))
      (node (ref "C151") (pin "1") (pinfunction "1_1") (pintype "passive"))
      (node (ref "C153") (pin "1") (pinfunction "1_1") (pintype "passive"))
      (node (ref "C154") (pin "1") (pinfunction "1_1") (pintype "passive"))
      (node (ref "C155") (pin "1") (pinfunction "1_1") (pintype "passive"))
      (node (ref "C156") (pin "1") (pinfunction "1_1") (pintype "passive"))
      (node (ref "C157") (pin "1") (pinfunction "1_1") (pintype "passive"))
      (node (ref "C158") (pin "1") (pinfunction "1_1") (pintype "passive"))
      (node (ref "C159") (pin "1") (pinfunction "1_1") (pintype "passive"))
      (node (ref "C160") (pin "1") (pinfunction "1_1") (pintype "passive"))
      (node (ref "C161") (pin "1") (pinfunction "1_1") (pintype "passive"))
      (node (ref "C162") (pin "1") (pinfunction "1_1") (pintype "passive"))
      (node (ref "C163") (pin "1") (pinfunction "1_1") (pintype "passive"))
      (node (ref "C164") (pin "2") (pinfunction "2_2") (pintype "passive"))
      (node (ref "C165") (pin "1") (pinfunction "1_1") (pintype "passive"))
      (node (ref "C166") (pin "1") (pinfunction "1_1") (pintype "passive"))
      (node (ref "C186") (pin "1") (pinfunction "1_1") (pintype "passive"))
      (node (ref "J1") (pin "8") (pinfunction "8_8") (pintype "bidirectional"))
      (node (ref "J2") (pin "8") (pinfunction "8_8") (pintype "bidirectional"))
      (node (ref "J3") (pin "8") (pinfunction "8_8") (pintype "bidirectional"))
      (node (ref "J4") (pin "8") (pinfunction "8_8") (pintype "bidirectional"))
      (node (ref "J5") (pin "8") (pinfunction "8_8") (pintype "bidirectional"))
      (node (ref "JM14") (pin "3") (pinfunction "3_3") (pintype "passive"))
      (node (ref "JM15") (pin "3") (pinfunction "3_3") (pintype "passive"))
      (node (ref "JM16") (pin "3") (pinfunction "3_3") (pintype "passive"))
      (node (ref "JM17") (pin "3") (pinfunction "3_3") (pintype "passive"))
      (node (ref "R44") (pin "2") (pinfunction "2_2") (pintype "passive"))
      (node (ref "R45") (pin "1") (pinfunction "1_1") (pintype "passive"))
      (node (ref "U11") (pin "116") (pinfunction "GNDD_116") (pintype "passive"))
      (node (ref "U11") (pin "12") (pinfunction "GNDA_12") (pintype "passive"))
      (node (ref "U11") (pin "124") (pinfunction "GNDA_124") (pintype "passive"))
      (node (ref "U11") (pin "126") (pinfunction "GNDA_126") (pintype "passive"))
      (node (ref "U11") (pin "127") (pinfunction "GNDA_127") (pintype "passive"))
      (node (ref "U11") (pin "16") (pinfunction "GNDA_16") (pintype "passive"))
      (node (ref "U11") (pin "2") (pinfunction "GNDA_2") (pintype "passive"))
      (node (ref "U11") (pin "21") (pinfunction "GNDA_21") (pintype "passive"))
      (node (ref "U11") (pin "27") (pinfunction "GNDA_27") (pintype "passive"))
      (node (ref "U11") (pin "30") (pinfunction "GNDA_30") (pintype "passive"))
      (node (ref "U11") (pin "34") (pinfunction "GNDA_34") (pintype "passive"))
      (node (ref "U11") (pin "40") (pinfunction "GNDA_40") (pintype "passive"))
      (node (ref "U11") (pin "42") (pinfunction "GNDA_42") (pintype "passive"))
      (node (ref "U11") (pin "44") (pinfunction "GNDA_44") (pintype "passive"))
      (node (ref "U11") (pin "49") (pinfunction "GNDD_49") (pintype "passive"))
      (node (ref "U11") (pin "58") (pinfunction "GNDD_58") (pintype "passive"))
      (node (ref "U11") (pin "6") (pinfunction "GNDA_6") (pintype "passive"))
      (node (ref "U11") (pin "76") (pinfunction "GNDD_76") (pintype "passive"))
      (node (ref "U11") (pin "88") (pinfunction "GNDD_88") (pintype "passive"))
      (node (ref "U11") (pin "99") (pinfunction "GNDD_99") (pintype "passive"))
      (node (ref "U12") (pin "3") (pinfunction "GND_3") (pintype "passive"))
      (node (ref "U12") (pin "6") (pinfunction "GND_6") (pintype "passive"))
      (node (ref "U12") (pin "7") (pinfunction "GND_7") (pintype "passive"))
      (node (ref "U16") (pin "1") (pinfunction "E0_1") (pintype "passive"))
      (node (ref "U16") (pin "2") (pinfunction "E1_2") (pintype "passive"))
      (node (ref "U16") (pin "3") (pinfunction "E2_3") (pintype "passive"))
      (node (ref "U16") (pin "4") (pinfunction "VSS_4") (pintype "passive"))
      (node (ref "U16") (pin "7") (pinfunction "~{WC}_7") (pintype "passive"))
    )
    (net (code "73") (name "Net-(D12-PadA)") (class "Default")
      (node (ref "D12") (pin "A") (pinfunction "A_A") (pintype "passive"))
      (node (ref "R84") (pin "1") (pinfunction "1_1") (pintype "passive"))
    )
    (net (code "74") (name "Net-(D13-PadA)") (class "Default")
      (node (ref "D13") (pin "A") (pinfunction "A_A") (pintype "passive"))
      (node (ref "R87") (pin "1") (pinfunction "1_1") (pintype "passive"))
    )
    (net (code "75") (name "Net-(D14-PadA)") (class "Default")
      (node (ref "D14") (pin "A") (pinfunction "A_A") (pintype "passive"))
      (node (ref "R88") (pin "1") (pinfunction "1_1") (pintype "passive"))
    )
    (net (code "76") (name "Net-(D15-PadA)") (class "Default")
      (node (ref "D15") (pin "A") (pinfunction "A_A") (pintype "passive"))
      (node (ref "R83") (pin "1") (pinfunction "1_1") (pintype "passive"))
    )
    (net (code "77") (name "Net-(D16-PadA)") (class "Default")
      (node (ref "D16") (pin "A") (pinfunction "A_A") (pintype "passive"))
      (node (ref "R89") (pin "1") (pinfunction "1_1") (pintype "passive"))
    )
    (net (code "78") (name "Net-(L3-Pad2)") (class "Default")
      (node (ref "L3") (pin "2") (pinfunction "2_2") (pintype "passive"))
      (node (ref "R44") (pin "1") (pinfunction "1_1") (pintype "passive"))
    )
    (net (code "79") (name "Net-(U11C-PCOL)") (class "Default")
      (node (ref "R54") (pin "2") (pinfunction "2_2") (pintype "passive"))
      (node (ref "U11") (pin "68") (pinfunction "PCOL_68") (pintype "passive"))
    )
    (net (code "80") (name "Net-(U11C-PCRS)") (class "Default")
      (node (ref "R52") (pin "2") (pinfunction "2_2") (pintype "passive"))
      (node (ref "U11") (pin "67") (pinfunction "PCRS_67") (pintype "passive"))
    )
    (net (code "81") (name "Net-(U11C-PMRXC)") (class "Default")
      (node (ref "R51") (pin "1") (pinfunction "1_1") (pintype "passive"))
      (node (ref "U11") (pin "60") (pinfunction "PMRXC_60") (pintype "passive"))
    )
    (net (code "82") (name "Net-(U11C-PMRXD0)") (class "Default")
      (node (ref "R46") (pin "1") (pinfunction "1_1") (pintype "passive"))
      (node (ref "U11") (pin "65") (pinfunction "PMRXD0_65") (pintype "passive"))
    )
    (net (code "83") (name "Net-(U11C-PMRXD1)") (class "Default")
      (node (ref "R47") (pin "1") (pinfunction "1_1") (pintype "passive"))
      (node (ref "U11") (pin "64") (pinfunction "PMRXD1_64") (pintype "passive"))
    )
    (net (code "84") (name "Net-(U11C-PMRXD2)") (class "Default")
      (node (ref "R48") (pin "1") (pinfunction "1_1") (pintype "passive"))
      (node (ref "U11") (pin "63") (pinfunction "PMRXD2_63") (pintype "passive"))
    )
    (net (code "85") (name "Net-(U11C-PMRXD3)") (class "Default")
      (node (ref "R49") (pin "1") (pinfunction "1_1") (pintype "passive"))
      (node (ref "U11") (pin "62") (pinfunction "PMRXD3_62") (pintype "passive"))
    )
    (net (code "86") (name "Net-(U11C-PMRXDV)") (class "Default")
      (node (ref "R50") (pin "1") (pinfunction "1_1") (pintype "passive"))
      (node (ref "U11") (pin "61") (pinfunction "PMRXDV_61") (pintype "passive"))
    )
    (net (code "87") (name "Net-(U11C-PMTXC)") (class "Default")
      (node (ref "R53") (pin "1") (pinfunction "1_1") (pintype "passive"))
      (node (ref "U11") (pin "57") (pinfunction "PMTXC_57") (pintype "passive"))
    )
    (net (code "88") (name "Net-(U11E-ISET)") (class "Default")
      (node (ref "R45") (pin "2") (pinfunction "2_2") (pintype "passive"))
      (node (ref "U11") (pin "17") (pinfunction "ISET_17") (pintype "passive"))
    )
    (net (code "89") (name "Net-(U11E-PWRDN_N)") (class "Default")
      (node (ref "R85") (pin "1") (pinfunction "1_1") (pintype "passive"))
      (node (ref "U11") (pin "47") (pinfunction "PWRDN_N_47") (pintype "passive"))
    )
    (net (code "90") (name "Net-(U11E-X1)") (class "Default")
      (node (ref "C165") (pin "2") (pinfunction "2_2") (pintype "passive"))
      (node (ref "U11") (pin "121") (pinfunction "X1_121") (pintype "passive"))
      (node (ref "X3") (pin "2") (pinfunction "OSC2_2") (pintype "passive"))
    )
    (net (code "91") (name "Net-(U11E-X2)") (class "Default")
      (node (ref "C164") (pin "1") (pinfunction "1_1") (pintype "passive"))
      (node (ref "U11") (pin "122") (pinfunction "X2_122") (pintype "passive"))
      (node (ref "X3") (pin "1") (pinfunction "OSC1_1") (pintype "passive"))
    )
    (net (code "92") (name "Net-(U16-SCL)") (class "Default")
      (node (ref "R55") (pin "2") (pinfunction "2_2") (pintype "passive"))
      (node (ref "R90") (pin "1") (pinfunction "1_1") (pintype "passive"))
      (node (ref "U16") (pin "6") (pinfunction "SCL_6") (pintype "passive"))
    )
    (net (code "93") (name "Net-(U16-SDA)") (class "Default")
      (node (ref "R56") (pin "2") (pinfunction "2_2") (pintype "passive"))
      (node (ref "R91") (pin "1") (pinfunction "1_1") (pintype "passive"))
      (node (ref "U16") (pin "5") (pinfunction "SDA_5") (pintype "passive"))
    )
    (net (code "94") (name "Vin") (class "Default")
      (node (ref "U12") (pin "1") (pinfunction "IN_1") (pintype "passive"))
      (node (ref "U12") (pin "4") (pinfunction "IN_4") (pintype "passive"))
      (node (ref "U12") (pin "8") (pinfunction "EN_8") (pintype "passive"))
    )
    (net (code "95") (name "unconnected-(C152-Pad1)") (class "Default")
      (node (ref "C152") (pin "1") (pinfunction "1_1") (pintype "passive"))
    )
    (net (code "96") (name "unconnected-(J1-Pad7)") (class "Default")
      (node (ref "J1") (pin "7") (pinfunction "7_7") (pintype "passive+no_connect"))
    )
    (net (code "97") (name "unconnected-(J2-Pad7)") (class "Default")
      (node (ref "J2") (pin "7") (pinfunction "7_7") (pintype "passive+no_connect"))
    )
    (net (code "98") (name "unconnected-(J3-Pad7)") (class "Default")
      (node (ref "J3") (pin "7") (pinfunction "7_7") (pintype "passive+no_connect"))
    )
    (net (code "99") (name "unconnected-(J4-Pad7)") (class "Default")
      (node (ref "J4") (pin "7") (pinfunction "7_7") (pintype "passive+no_connect"))
    )
    (net (code "100") (name "unconnected-(J5-Pad7)") (class "Default")
      (node (ref "J5") (pin "7") (pinfunction "7_7") (pintype "passive+no_connect"))
    )
    (net (code "101") (name "unconnected-(U11D-FXSD4-Pad39)") (class "Default")
      (node (ref "U11") (pin "39") (pinfunction "FXSD4_39") (pintype "passive+no_connect"))
    )
    (net (code "102") (name "unconnected-(U11D-FXSD5-Pad38)") (class "Default")
      (node (ref "U11") (pin "38") (pinfunction "FXSD5_38") (pintype "passive+no_connect"))
    )
    (net (code "103") (name "unconnected-(U11D-MDI-XDIS-Pad1)") (class "Default")
      (node (ref "U11") (pin "1") (pinfunction "MDI-XDIS_1") (pintype "passive+no_connect"))
    )
    (net (code "104") (name "unconnected-(U11D-MUX1-Pad45)") (class "Default")
      (node (ref "U11") (pin "45") (pinfunction "MUX1_45") (pintype "passive+no_connect"))
    )
    (net (code "105") (name "unconnected-(U11D-MUX2-Pad46)") (class "Default")
      (node (ref "U11") (pin "46") (pinfunction "MUX2_46") (pintype "passive+no_connect"))
    )
    (net (code "106") (name "unconnected-(U11D-NC-Pad120)") (class "Default")
      (node (ref "U11") (pin "120") (pinfunction "NC_120") (pintype "passive+no_connect"))
    )
    (net (code "107") (name "unconnected-(U11D-RESERVE-Pad48)") (class "Default")
      (node (ref "U11") (pin "48") (pinfunction "RESERVE_48") (pintype "passive+no_connect"))
    )
    (net (code "108") (name "unconnected-(U11D-SCANEN-Pad119)") (class "Default")
      (node (ref "U11") (pin "119") (pinfunction "SCANEN_119") (pintype "passive+no_connect"))
    )
    (net (code "109") (name "unconnected-(U11D-SCOL-Pad84)") (class "Default")
      (node (ref "U11") (pin "84") (pinfunction "SCOL_84") (pintype "passive+no_connect"))
    )
    (net (code "110") (name "unconnected-(U11D-SCRS-Pad85)") (class "Default")
      (node (ref "U11") (pin "85") (pinfunction "SCRS_85") (pintype "passive+no_connect"))
    )
    (net (code "111") (name "unconnected-(U11D-SMRXC-Pad78)") (class "Default")
      (node (ref "U11") (pin "78") (pinfunction "SMRXC_78") (pintype "passive+no_connect"))
    )
    (net (code "112") (name "unconnected-(U11D-SMRXD0-Pad83)") (class "Default")
      (node (ref "U11") (pin "83") (pinfunction "SMRXD0_83") (pintype "passive+no_connect"))
    )
    (net (code "113") (name "unconnected-(U11D-SMRXD1-Pad82)") (class "Default")
      (node (ref "U11") (pin "82") (pinfunction "SMRXD1_82") (pintype "passive+no_connect"))
    )
    (net (code "114") (name "unconnected-(U11D-SMRXD2-Pad81)") (class "Default")
      (node (ref "U11") (pin "81") (pinfunction "SMRXD2_81") (pintype "passive+no_connect"))
    )
    (net (code "115") (name "unconnected-(U11D-SMRXD3-Pad80)") (class "Default")
      (node (ref "U11") (pin "80") (pinfunction "SMRXD3_80") (pintype "passive+no_connect"))
    )
    (net (code "116") (name "unconnected-(U11D-SMRXDV-Pad79)") (class "Default")
      (node (ref "U11") (pin "79") (pinfunction "SMRXDV_79") (pintype "passive+no_connect"))
    )
    (net (code "117") (name "unconnected-(U11D-SMTXC-Pad75)") (class "Default")
      (node (ref "U11") (pin "75") (pinfunction "SMTXC_75") (pintype "passive+no_connect"))
    )
    (net (code "118") (name "unconnected-(U11D-SMTXD0-Pad73)") (class "Default")
      (node (ref "U11") (pin "73") (pinfunction "SMTXD0_73") (pintype "passive+no_connect"))
    )
    (net (code "119") (name "unconnected-(U11D-SMTXD1-Pad72)") (class "Default")
      (node (ref "U11") (pin "72") (pinfunction "SMTXD1_72") (pintype "passive+no_connect"))
    )
    (net (code "120") (name "unconnected-(U11D-SMTXD2-Pad71)") (class "Default")
      (node (ref "U11") (pin "71") (pinfunction "SMTXD2_71") (pintype "passive+no_connect"))
    )
    (net (code "121") (name "unconnected-(U11D-SMTXD3-Pad70)") (class "Default")
      (node (ref "U11") (pin "70") (pinfunction "SMTXD3_70") (pintype "passive+no_connect"))
    )
    (net (code "122") (name "unconnected-(U11D-SMTXEN-Pad69)") (class "Default")
      (node (ref "U11") (pin "69") (pinfunction "SMTXEN_69") (pintype "passive+no_connect"))
    )
    (net (code "123") (name "unconnected-(U11D-SMTXER-Pad74)") (class "Default")
      (node (ref "U11") (pin "74") (pinfunction "SMTXER_74") (pintype "passive+no_connect"))
    )
    (net (code "124") (name "unconnected-(U11D-TEST2-Pad128)") (class "Default")
      (node (ref "U11") (pin "128") (pinfunction "TEST2_128") (pintype "passive+no_connect"))
    )
    (net (code "125") (name "unconnected-(U11D-TESTEN-Pad118)") (class "Default")
      (node (ref "U11") (pin "118") (pinfunction "TESTEN_118") (pintype "passive+no_connect"))
    )
    (net (code "126") (name "unconnected-(U12-NC-Pad5)") (class "Default")
      (node (ref "U12") (pin "5") (pinfunction "NC_5") (pintype "passive"))
    )
  )
)
